# Supply_3V0.net
KiCad netlist of a schematic drawn in Altium Designer
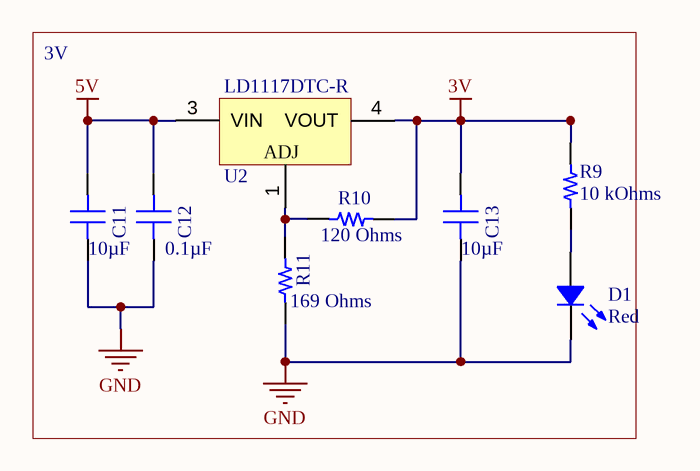
[diagram p0: Supply_3V0.SchDoc]

(export (version "E")
  (design (tool "Eeschema 10.0.6"))
  (components
    (comp (ref "C11")
      (value "10µF")
      (footprint "CAP 0805_2012")
      (description "CAP CER 10UF 16V X5R 0805")
      (fields (field (name "TOLERANCE") "±10%") (field (name "PART NUMBER") "0805YD106KAT2A"))
      (libsource (lib "Celestial Altium Library - altium_library") (part "Capacitor"))
    )
    (comp (ref "C12")
      (value "~")
      (footprint "CAP 0805_2012")
      (description "CAP CER 0.1UF 25V Z5U 0805")
      (fields
        (field (name "TOLERANCE") "-20%, +80%")
        (field (name "PART NUMBER") "08053E104ZAT2A")
        (field (name "CAPACITANCE") "0.1µF")
      )
      (libsource (lib "Celestial Altium Library - altium_library") (part "Capacitor"))
    )
    (comp (ref "C13")
      (value "10µF")
      (footprint "CAP 0805_2012")
      (description "CAP CER 10UF 16V X5R 0805")
      (fields (field (name "TOLERANCE") "±10%") (field (name "PART NUMBER") "0805YD106KAT2A"))
      (libsource (lib "Celestial Altium Library - altium_library") (part "Capacitor"))
    )
    (comp (ref "D1")
      (value "Red")
      (footprint "LED 0603_1608 RED")
      (description "LED RED CLEAR 0603 SMD")
      (fields
        (field (name "PART NUMBER") "LR Q976.01-P2R2-1")
        (field (name "MANUFACTURER") "ams-OSRAM USA Inc.")
      )
      (libsource (lib "Celestial Altium Library - altium_library") (part "LED"))
    )
    (comp (ref "R9")
      (value "10 kOhms")
      (footprint "YAGEO RES 0603_1608")
      (description "RES SMD 10K OHM 5% 1/10W 0603")
      (fields (field (name "PART NUMBER") "AC0603JR-0710KL") (field (name "MANUFACTURER") "Yageo"))
      (libsource (lib "Celestial Altium Library - altium_library") (part "Resistor"))
    )
    (comp (ref "R10")
      (value "120 Ohms")
      (footprint "YAGEO RES 0603_1608")
      (description "RES SMD 120 OHM 0.5% 1/10W 0603")
      (fields (field (name "TOLERANCE") "±0.5%") (field (name "PART NUMBER") "RT0603DRE07120RL"))
      (libsource (lib "Celestial Altium Library - altium_library") (part "Resistor"))
    )
    (comp (ref "R11")
      (value "169 Ohms")
      (footprint "YAGEO RES 0603_1608")
      (description "RES SMD 169 OHM 0.5% 1/10W 0603")
      (fields (field (name "TOLERANCE") "±0.5%") (field (name "PART NUMBER") "RT0603DRE07169RL"))
      (libsource (lib "Celestial Altium Library - altium_library") (part "Resistor"))
    )
    (comp (ref "U2")
      (value "LD1117DTC-R")
      (footprint "DPAK456P1010X240-3N")
      (description "Adjustable Low Drop Voltage Regulator, 1.25 to 15V, 3-Pin DPAK, Tape and Reel")
      (libsource (lib "LD1117DTC_R") (part "LD1117DTC-R"))
    )
  )
  (nets
    (net (code "1") (name "3V") (class "Default")
      (node (ref "C13") (pin "1") (pinfunction "1_1") (pintype "passive"))
      (node (ref "R10") (pin "2") (pinfunction "2_2") (pintype "passive"))
      (node (ref "R9") (pin "2") (pinfunction "2_2") (pintype "passive"))
      (node (ref "U2") (pin "4") (pinfunction "VOUT_4") (pintype "power_in"))
    )
    (net (code "2") (name "5V") (class "Default")
      (node (ref "C11") (pin "1") (pinfunction "1_1") (pintype "passive"))
      (node (ref "C12") (pin "1") (pinfunction "1_1") (pintype "passive"))
      (node (ref "U2") (pin "3") (pinfunction "VIN_3") (pintype "power_in"))
    )
    (net (code "3") (name "GND") (class "Default")
      (node (ref "C11") (pin "2") (pinfunction "2_2") (pintype "passive"))
      (node (ref "C12") (pin "2") (pinfunction "2_2") (pintype "passive"))
      (node (ref "C13") (pin "2") (pinfunction "2_2") (pintype "passive"))
      (node (ref "D1") (pin "2") (pinfunction "2_2") (pintype "passive"))
      (node (ref "R11") (pin "2") (pinfunction "2_2") (pintype "passive"))
    )
    (net (code "4") (name "Net-(D1-Pad1)") (class "Default")
      (node (ref "D1") (pin "1") (pinfunction "1_1") (pintype "passive"))
      (node (ref "R9") (pin "1") (pinfunction "1_1") (pintype "passive"))
    )
    (net (code "5") (name "Net-(U2-GND)") (class "Default")
      (node (ref "R10") (pin "1") (pinfunction "1_1") (pintype "passive"))
      (node (ref "R11") (pin "1") (pinfunction "1_1") (pintype "passive"))
      (node (ref "U2") (pin "1") (pinfunction "GND_1") (pintype "power_in"))
    )
  )
)
